# schematic.net
KiCad netlist of a schematic drawn in EasyEDA
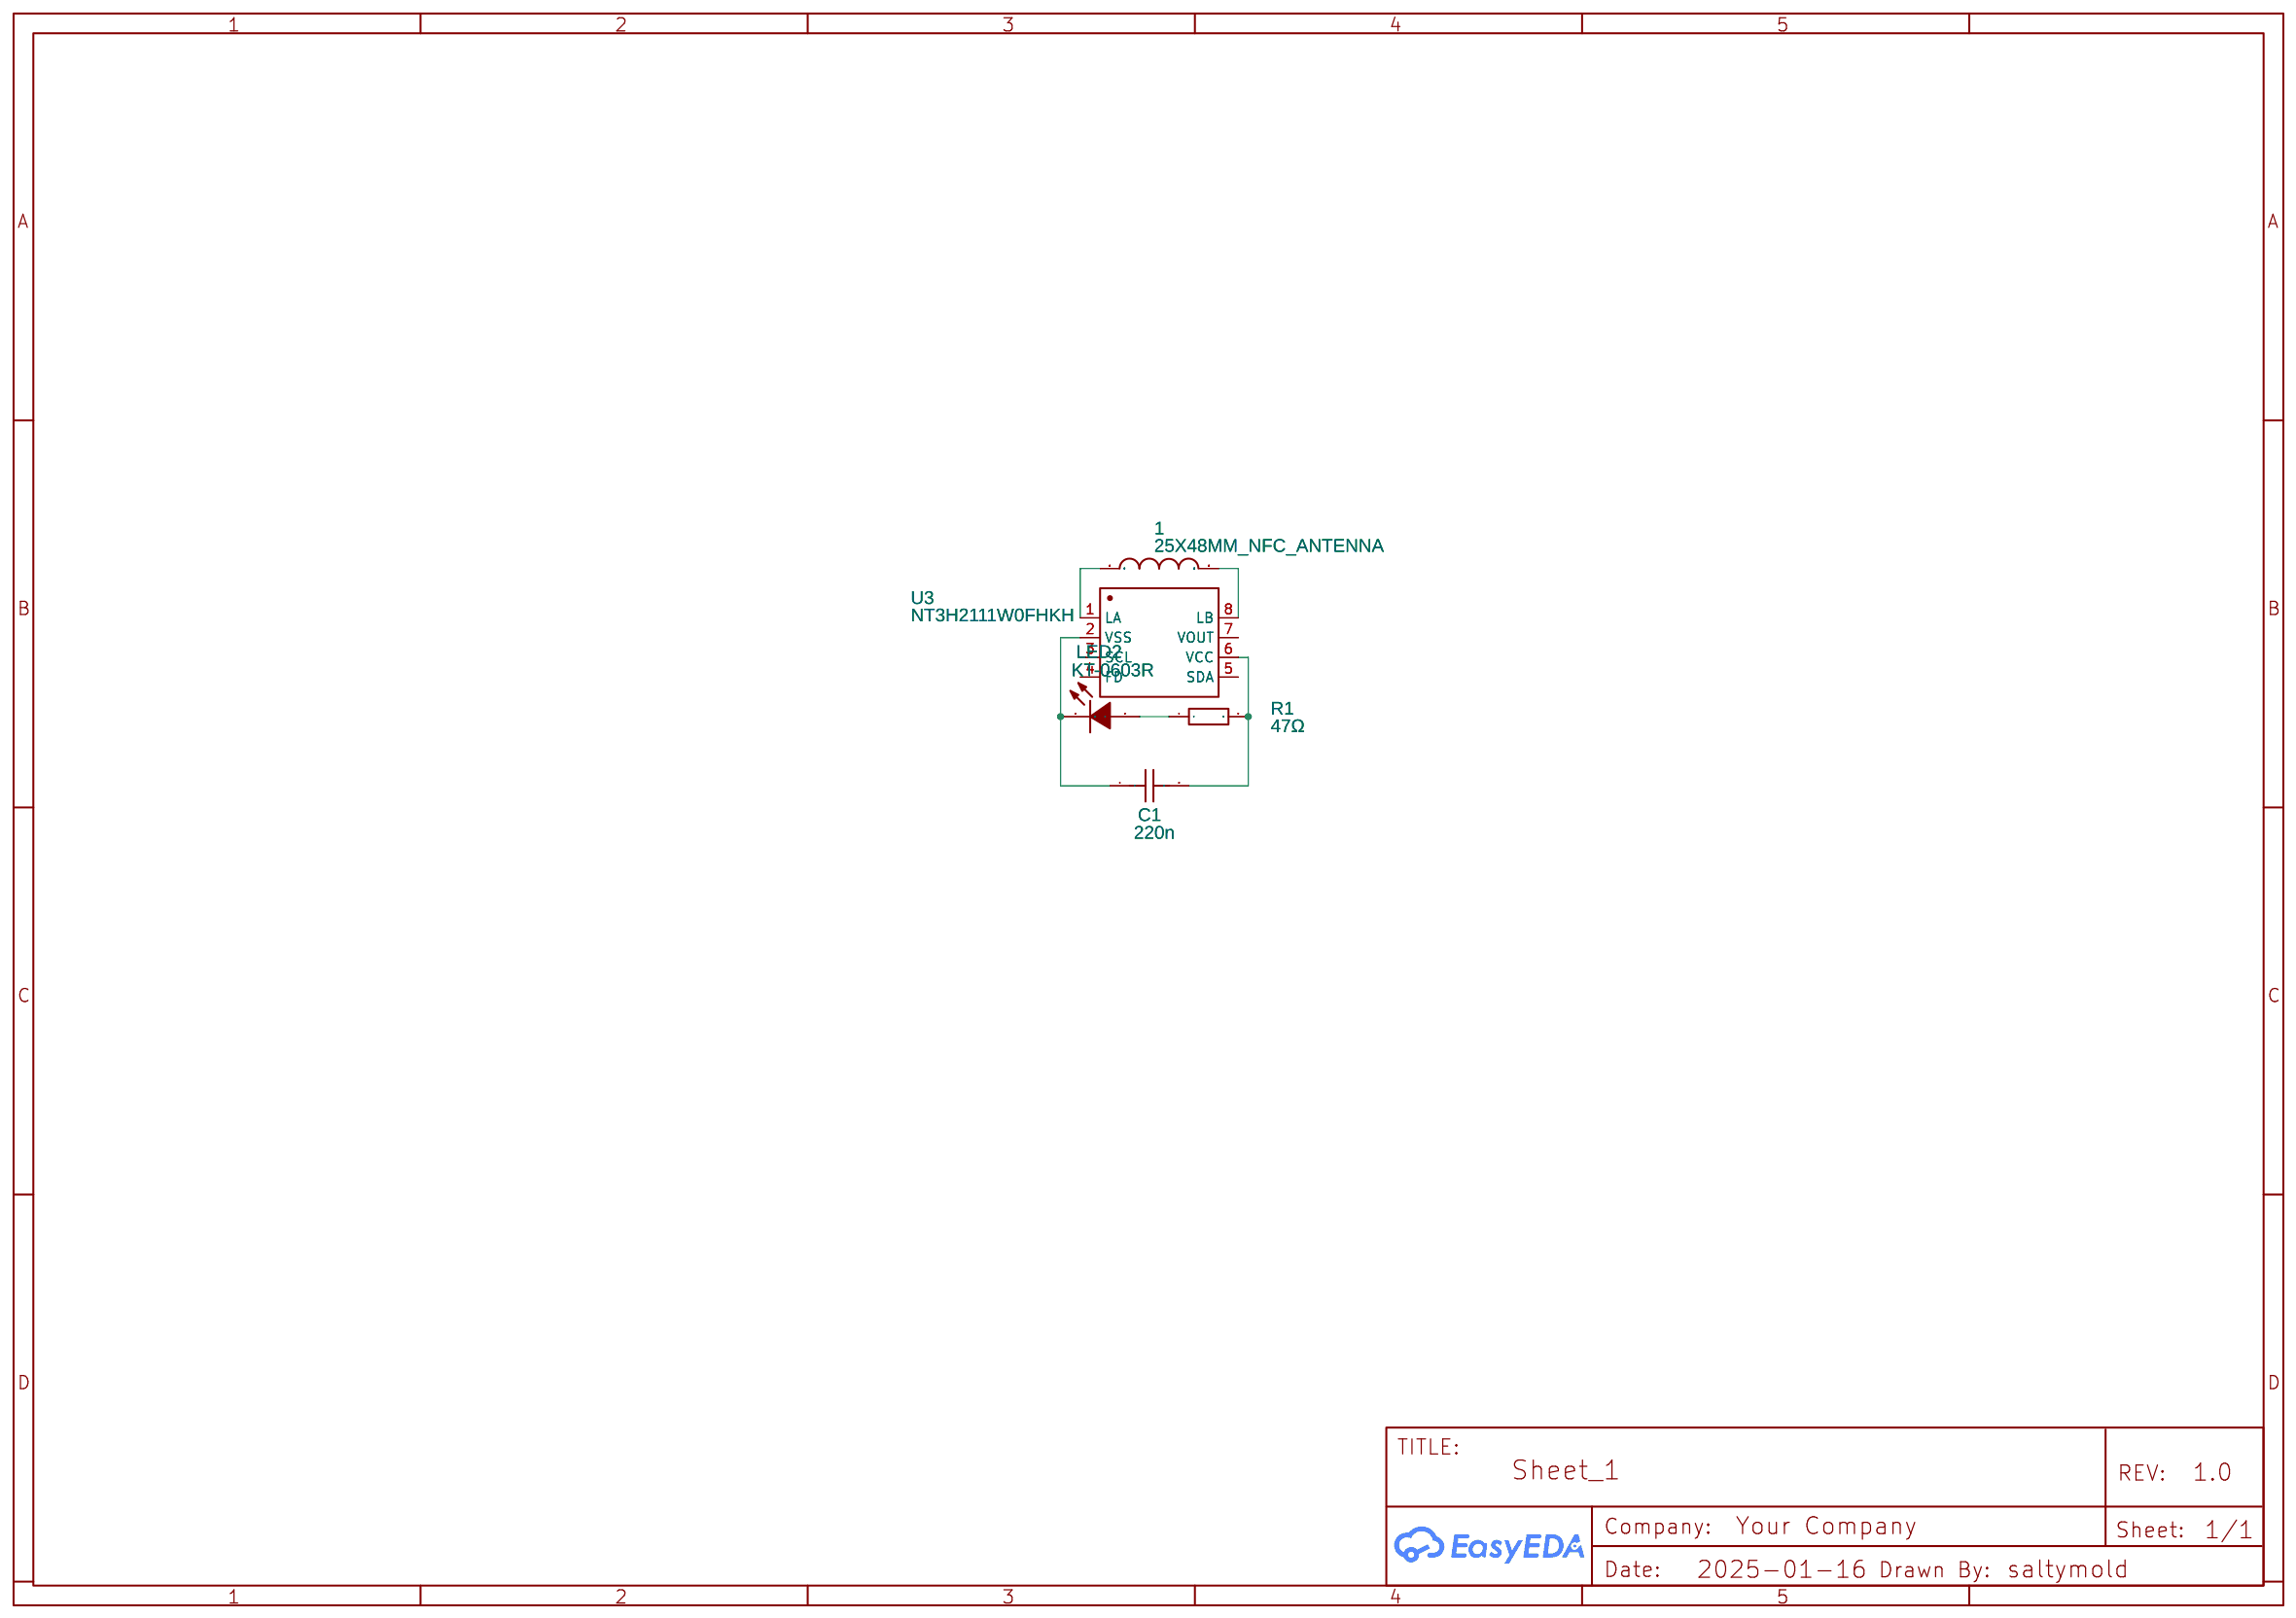
[diagram p0: schematic sheet]

(export (version "E")
  (design (tool "Eeschema 10.0.6"))
  (components
    (comp (ref "1") (value "25X48MM_NFC_ANTENNA") (libsource (lib "") (part "25X48MM_NFC_ANTENNA")))
    (comp (ref "C1") (value "220n") (libsource (lib "") (part "C_0603_US")))
    (comp (ref "LED2")
      (value "KT-0603R")
      (fields (field (name "Manufacturer") "KENTO"))
      (libsource (lib "") (part "KT-0603R"))
    )
    (comp (ref "R1")
      (value "47Ω")
      (fields
        (field (name "Manufacturer Part") "0603WAF470JT5E")
        (field (name "Manufacturer") "UNI-ROYAL(厚声)")
      )
      (libsource (lib "") (part "0603WAF470JT5E"))
    )
    (comp (ref "U3")
      (value "NT3H2111W0FHKH")
      (fields (field (name "Manufacturer") "NXP(恩智浦)"))
      (libsource (lib "") (part "NT3H2111W0FHKH"))
    )
  )
  (nets
    (net (code "1") (name "Net-(LED2-A)") (class "Default")
      (node (ref "LED2") (pin "2") (pinfunction "A_2") (pintype "unspecified"))
      (node (ref "R1") (pin "1") (pinfunction "1_1") (pintype "input"))
    )
    (net (code "2") (name "Net-(LED2-K)") (class "Default")
      (node (ref "C1") (pin "1") (pinfunction "1_1") (pintype "unspecified"))
      (node (ref "LED2") (pin "1") (pinfunction "K_1") (pintype "unspecified"))
      (node (ref "U3") (pin "2") (pinfunction "VSS_2") (pintype "unspecified"))
    )
    (net (code "3") (name "Net-(U3-LA)") (class "Default")
      (node (ref "1") (pin "P$1") (pinfunction "P$1_P$1") (pintype "bidirectional"))
      (node (ref "U3") (pin "1") (pinfunction "LA_1") (pintype "unspecified"))
    )
    (net (code "4") (name "Net-(U3-LB)") (class "Default")
      (node (ref "1") (pin "P$2") (pinfunction "P$2_P$2") (pintype "bidirectional"))
      (node (ref "U3") (pin "8") (pinfunction "LB_8") (pintype "unspecified"))
    )
    (net (code "5") (name "Net-(U3-VCC)") (class "Default")
      (node (ref "C1") (pin "2") (pinfunction "2_2") (pintype "unspecified"))
      (node (ref "R1") (pin "2") (pinfunction "2_2") (pintype "input"))
      (node (ref "U3") (pin "6") (pinfunction "VCC_6") (pintype "unspecified"))
    )
    (net (code "6") (name "unconnected-(U3-FD-Pad4)") (class "Default")
      (node (ref "U3") (pin "4") (pinfunction "FD_4") (pintype "unspecified"))
    )
    (net (code "7") (name "unconnected-(U3-SCL-Pad3)") (class "Default")
      (node (ref "U3") (pin "3") (pinfunction "SCL_3") (pintype "unspecified"))
    )
    (net (code "8") (name "unconnected-(U3-SDA-Pad5)") (class "Default")
      (node (ref "U3") (pin "5") (pinfunction "SDA_5") (pintype "unspecified"))
    )
    (net (code "9") (name "unconnected-(U3-VOUT-Pad7)") (class "Default")
      (node (ref "U3") (pin "7") (pinfunction "VOUT_7") (pintype "unspecified"))
    )
  )
)
